# X15_Brickstribution.net
KiCad netlist of a schematic drawn in EAGLE
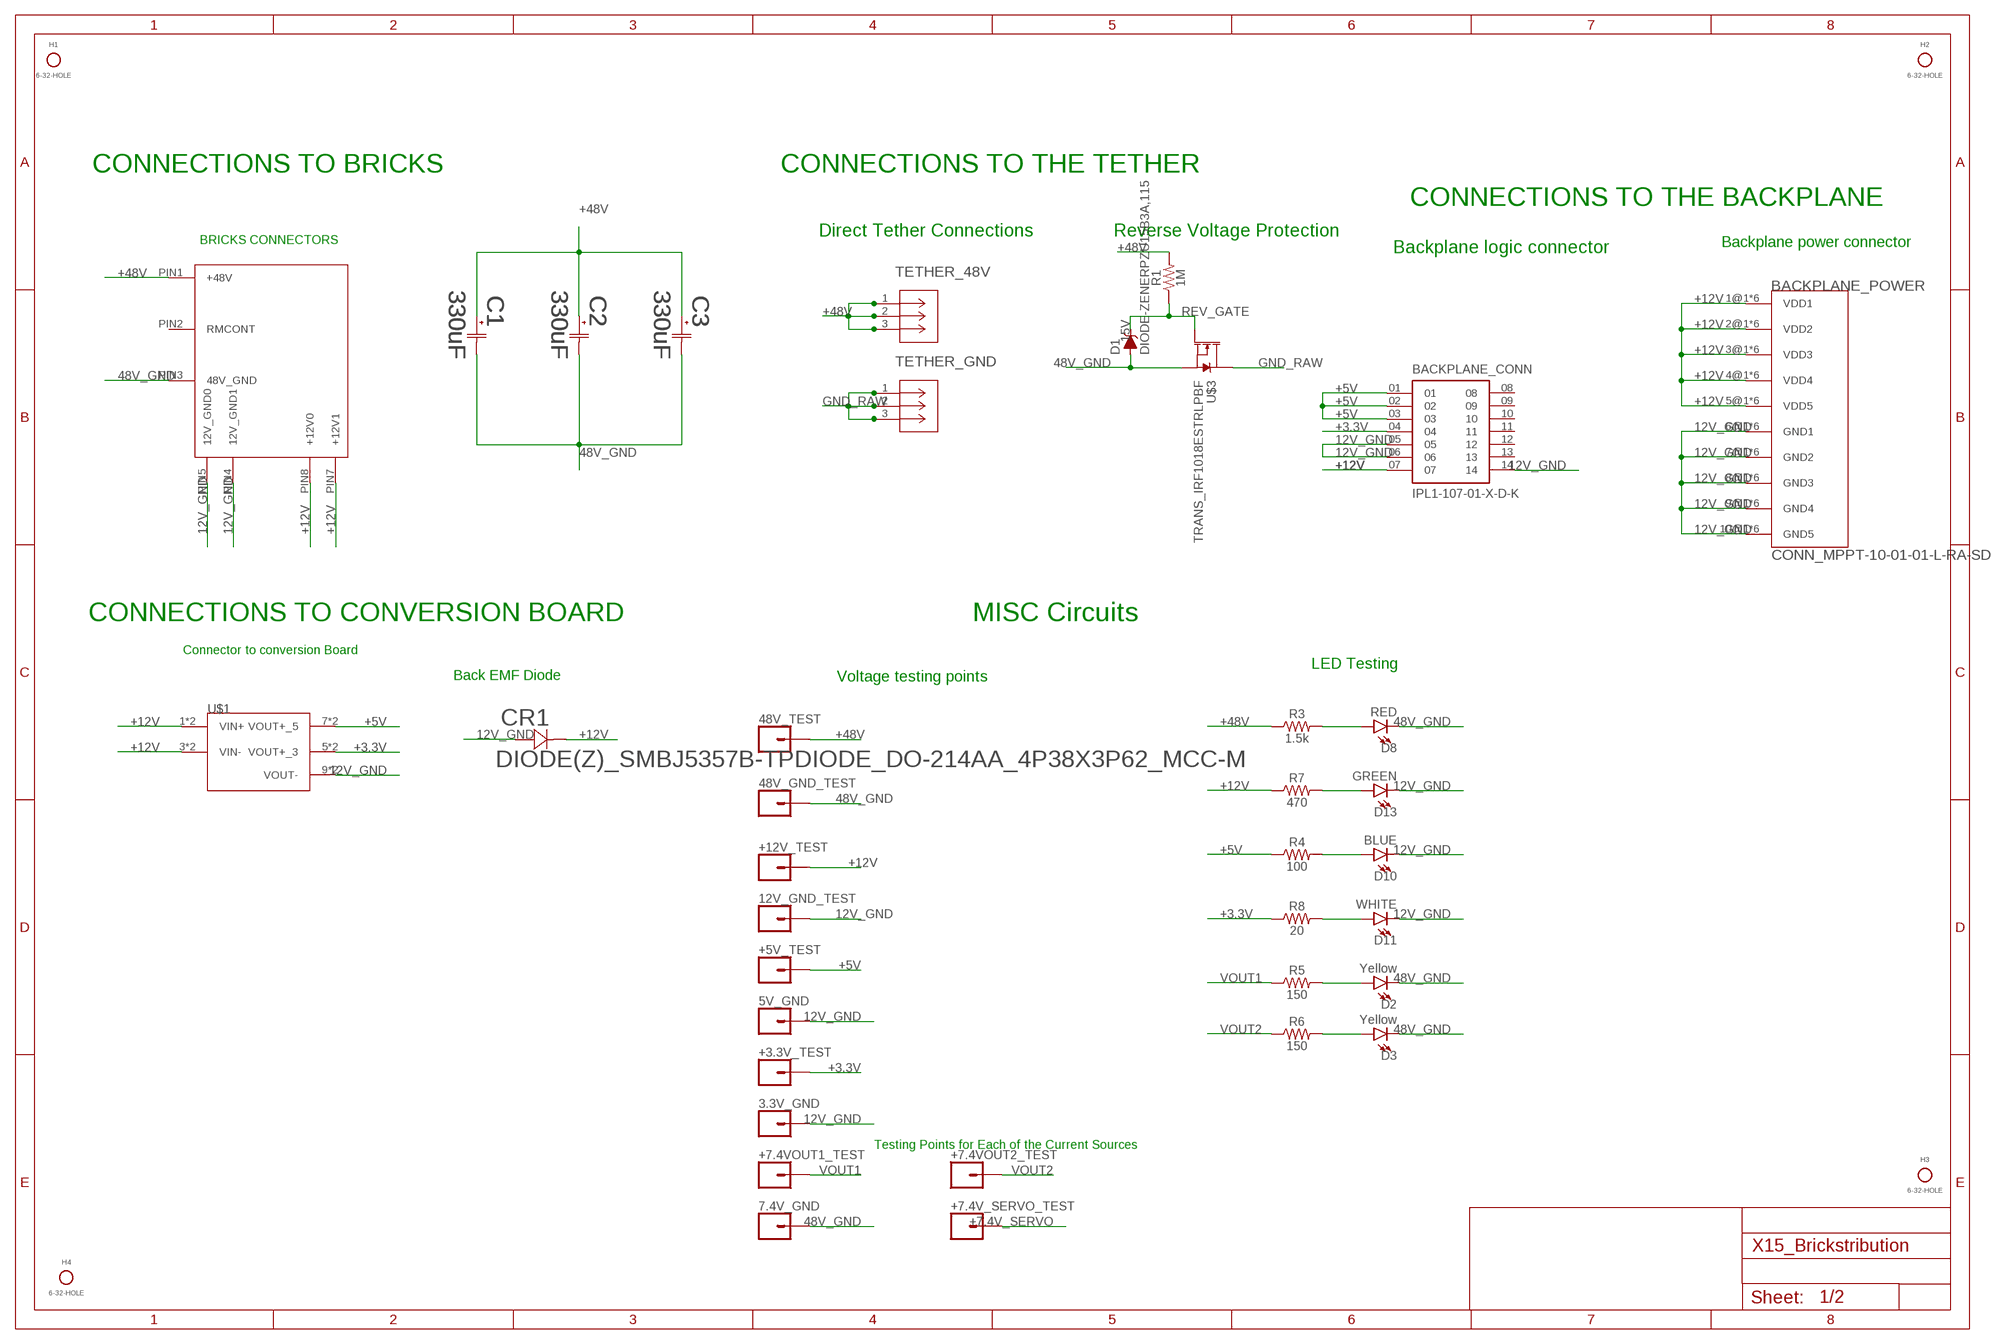
[diagram p0: schematic, sheet 1]
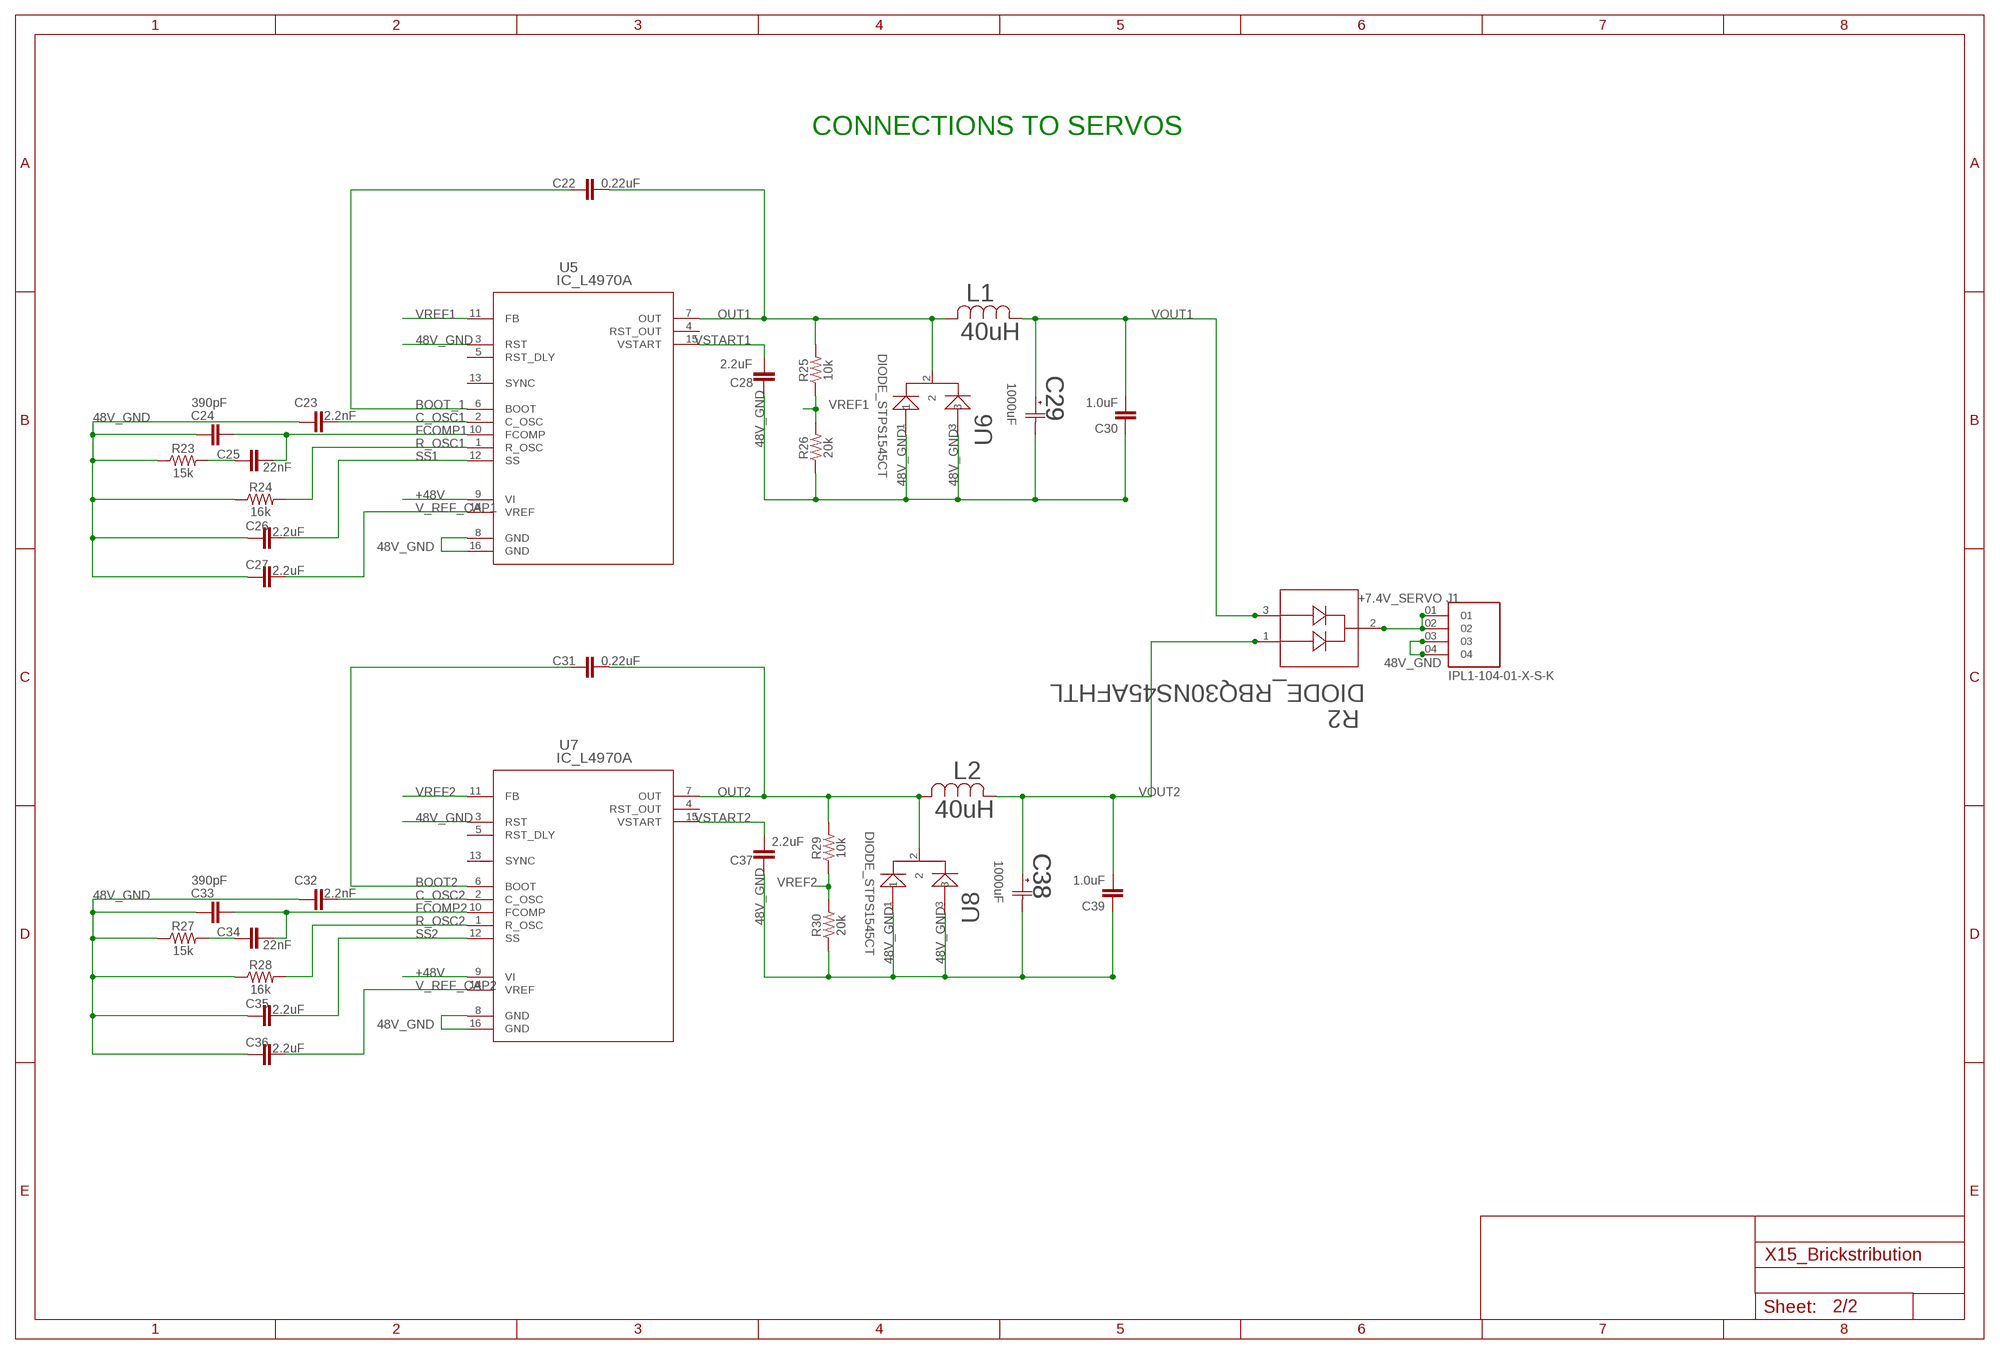
[diagram p1: schematic, sheet 2]

(export (version "E")
  (design (tool "Eeschema 10.0.6"))
  (components
    (comp (ref "C22")
      (value "0.22uF")
      (footprint "eagle-import:0603")
      (libsource (lib "eagle-import") (part "0.22UF-0603-25V-10%"))
    )
    (comp (ref "C23")
      (value "2.2nF")
      (footprint "eagle-import:0603")
      (libsource (lib "eagle-import") (part "2.2NF/2200PF-0603-50V-10%"))
    )
    (comp (ref "C24")
      (value "390pF")
      (footprint "eagle-import:0603")
      (libsource (lib "eagle-import") (part "390NF-0603-10V-10%"))
    )
    (comp (ref "C25")
      (value "22nF")
      (footprint "eagle-import:0603")
      (libsource (lib "eagle-import") (part "22NF/22,000PF-0603-50V-10%"))
    )
    (comp (ref "C26")
      (value "2.2uF")
      (footprint "eagle-import:0603")
      (libsource (lib "eagle-import") (part "2.2UF-0603-10V-20%"))
    )
    (comp (ref "C27")
      (value "2.2uF")
      (footprint "eagle-import:0603")
      (libsource (lib "eagle-import") (part "2.2UF-0603-10V-20%"))
    )
    (comp (ref "C28")
      (value "2.2uF")
      (footprint "eagle-import:0603")
      (libsource (lib "eagle-import") (part "2.2UF-0603-10V-20%"))
    )
    (comp (ref "C29")
      (value "1000uF")
      (footprint "eagle-import:CAP_PC_10X12P7_NCH-M")
      (fields
        (field (name "MANUFACTURER_PART_NUMBER") "PCG1A102MCL1GS")
        (field (name "COPYRIGHT") "Copyright (C) 2022 Ultra Librarian. All rights reserved.")
      )
      (libsource (lib "eagle-import") (part "CAP_PCG1A102MCL1GSCAP_PC_10X12P7_NCH-M"))
    )
    (comp (ref "C30")
      (value "1.0uF")
      (footprint "eagle-import:0603")
      (libsource (lib "eagle-import") (part "1.0UF-0603-16V-10%"))
    )
    (comp (ref "C31")
      (value "0.22uF")
      (footprint "eagle-import:0603")
      (libsource (lib "eagle-import") (part "0.22UF-0603-25V-10%"))
    )
    (comp (ref "C32")
      (value "2.2nF")
      (footprint "eagle-import:0603")
      (libsource (lib "eagle-import") (part "2.2NF/2200PF-0603-50V-10%"))
    )
    (comp (ref "C33")
      (value "390pF")
      (footprint "eagle-import:0603")
      (libsource (lib "eagle-import") (part "390NF-0603-10V-10%"))
    )
    (comp (ref "C34")
      (value "22nF")
      (footprint "eagle-import:0603")
      (libsource (lib "eagle-import") (part "22NF/22,000PF-0603-50V-10%"))
    )
    (comp (ref "C35")
      (value "2.2uF")
      (footprint "eagle-import:0603")
      (libsource (lib "eagle-import") (part "2.2UF-0603-10V-20%"))
    )
    (comp (ref "C36")
      (value "2.2uF")
      (footprint "eagle-import:0603")
      (libsource (lib "eagle-import") (part "2.2UF-0603-10V-20%"))
    )
    (comp (ref "C37")
      (value "2.2uF")
      (footprint "eagle-import:0603")
      (libsource (lib "eagle-import") (part "2.2UF-0603-10V-20%"))
    )
    (comp (ref "C38")
      (value "1000uF")
      (footprint "eagle-import:CAP_PC_10X12P7_NCH-M")
      (fields
        (field (name "MANUFACTURER_PART_NUMBER") "PCG1A102MCL1GS")
        (field (name "COPYRIGHT") "Copyright (C) 2022 Ultra Librarian. All rights reserved.")
      )
      (libsource (lib "eagle-import") (part "CAP_PCG1A102MCL1GSCAP_PC_10X12P7_NCH-M"))
    )
    (comp (ref "C39")
      (value "1.0uF")
      (footprint "eagle-import:0603")
      (libsource (lib "eagle-import") (part "1.0UF-0603-16V-10%"))
    )
    (comp (ref "J1")
      (value "IPL1-104-01-X-S-K")
      (footprint "eagle-import:SAMTEC_IPL1-104-01-X-S-K")
      (fields (field (name "MANUFACTURER") "SAMTEC"))
      (libsource (lib "eagle-import") (part "IPL1-104-01-X-S-K"))
    )
    (comp (ref "L1")
      (value "40uH")
      (footprint "eagle-import:IND_23XX-V_53_53")
      (fields
        (field (name "MANUFACTURER_PART_NUMBER") "2308-V-RC")
        (field (name "COPYRIGHT") "Copyright (C) 2022 Ultra Librarian. All rights reserved.")
      )
      (libsource (lib "eagle-import") (part "IND_2308-V-RC"))
    )
    (comp (ref "L2")
      (value "40uH")
      (footprint "eagle-import:IND_23XX-V_53_53")
      (fields
        (field (name "MANUFACTURER_PART_NUMBER") "2308-V-RC")
        (field (name "COPYRIGHT") "Copyright (C) 2022 Ultra Librarian. All rights reserved.")
      )
      (libsource (lib "eagle-import") (part "IND_2308-V-RC"))
    )
    (comp (ref "R2")
      (value "DIODE_RBQ30NS45AFHTL")
      (footprint "eagle-import:TRANS_R5009FNJ_ROM")
      (fields
        (field (name "MANUFACTURER_PART_NUMBER") "RBQ30NS45AFHTL")
        (field (name "COPYRIGHT") "Copyright (C) 2022 Ultra Librarian. All rights reserved.")
      )
      (libsource (lib "eagle-import") (part "DIODE_RBQ30NS45AFHTL"))
    )
    (comp (ref "R23")
      (value "15k")
      (footprint "eagle-import:0603")
      (libsource (lib "eagle-import") (part "15KOHM-0603-1/10W-1%"))
    )
    (comp (ref "R24")
      (value "16k")
      (footprint "eagle-import:0603")
      (libsource (lib "eagle-import") (part "16.2KOHM-0603-1/10W-1%"))
    )
    (comp (ref "R25")
      (value "10k")
      (footprint "eagle-import:0603")
      (libsource (lib "eagle-import") (part "10KOHM-0603-1/10W-1%"))
    )
    (comp (ref "R26")
      (value "20k")
      (footprint "eagle-import:0603")
      (libsource (lib "eagle-import") (part "20KOHM-0603-1/10W-1%"))
    )
    (comp (ref "R27")
      (value "15k")
      (footprint "eagle-import:0603")
      (libsource (lib "eagle-import") (part "15KOHM-0603-1/10W-1%"))
    )
    (comp (ref "R28")
      (value "16k")
      (footprint "eagle-import:0603")
      (libsource (lib "eagle-import") (part "16.2KOHM-0603-1/10W-1%"))
    )
    (comp (ref "R29")
      (value "10k")
      (footprint "eagle-import:0603")
      (libsource (lib "eagle-import") (part "10KOHM-0603-1/10W-1%"))
    )
    (comp (ref "R30")
      (value "20k")
      (footprint "eagle-import:0603")
      (libsource (lib "eagle-import") (part "20KOHM-0603-1/10W-1%"))
    )
    (comp (ref "U5")
      (value "IC_L4970A")
      (footprint "eagle-import:MULTIWATT15_V_STM")
      (fields
        (field (name "MANUFACTURER_PART_NUMBER") "L4970A")
        (field (name "COPYRIGHT") "Copyright (C) 2022 Ultra Librarian. All rights reserved.")
      )
      (libsource (lib "eagle-import") (part "IC_L4970A"))
    )
    (comp (ref "U6")
      (value "DIODE_STPS1545CT")
      (footprint "eagle-import:TO-220AB_STM")
      (fields
        (field (name "MANUFACTURER_PART_NUMBER") "STPS1545CT")
        (field (name "COPYRIGHT") "Copyright (C) 2022 Ultra Librarian. All rights reserved.")
      )
      (libsource (lib "eagle-import") (part "DIODE_STPS1545CT"))
    )
    (comp (ref "U7")
      (value "IC_L4970A")
      (footprint "eagle-import:MULTIWATT15_V_STM")
      (fields
        (field (name "MANUFACTURER_PART_NUMBER") "L4970A")
        (field (name "COPYRIGHT") "Copyright (C) 2022 Ultra Librarian. All rights reserved.")
      )
      (libsource (lib "eagle-import") (part "IC_L4970A"))
    )
    (comp (ref "U8")
      (value "DIODE_STPS1545CT")
      (footprint "eagle-import:TO-220AB_STM")
      (fields
        (field (name "MANUFACTURER_PART_NUMBER") "STPS1545CT")
        (field (name "COPYRIGHT") "Copyright (C) 2022 Ultra Librarian. All rights reserved.")
      )
      (libsource (lib "eagle-import") (part "DIODE_STPS1545CT"))
    )
    (comp (ref "+3.3V_TEST")
      (value "CONN_01")
      (footprint "eagle-import:1X01")
      (libsource (lib "eagle-import") (part "CONN_01"))
    )
    (comp (ref "+5V_TEST")
      (value "CONN_01")
      (footprint "eagle-import:1X01")
      (libsource (lib "eagle-import") (part "CONN_01"))
    )
    (comp (ref "+7.4VOUT1_TEST")
      (value "CONN_01")
      (footprint "eagle-import:1X01")
      (libsource (lib "eagle-import") (part "CONN_01"))
    )
    (comp (ref "+7.4VOUT2_TEST")
      (value "CONN_01")
      (footprint "eagle-import:1X01")
      (libsource (lib "eagle-import") (part "CONN_01"))
    )
    (comp (ref "+7.4V_SERVO_TEST")
      (value "CONN_01")
      (footprint "eagle-import:1X01")
      (libsource (lib "eagle-import") (part "CONN_01"))
    )
    (comp (ref "+12V_TEST")
      (value "CONN_01")
      (footprint "eagle-import:1X01")
      (libsource (lib "eagle-import") (part "CONN_01"))
    )
    (comp (ref "3.3V_GND")
      (value "CONN_01")
      (footprint "eagle-import:1X01")
      (libsource (lib "eagle-import") (part "CONN_01"))
    )
    (comp (ref "5V_GND")
      (value "CONN_01")
      (footprint "eagle-import:1X01")
      (libsource (lib "eagle-import") (part "CONN_01"))
    )
    (comp (ref "7.4V_GND")
      (value "CONN_01")
      (footprint "eagle-import:1X01")
      (libsource (lib "eagle-import") (part "CONN_01"))
    )
    (comp (ref "12V_GND_TEST")
      (value "CONN_01")
      (footprint "eagle-import:1X01")
      (libsource (lib "eagle-import") (part "CONN_01"))
    )
    (comp (ref "48V_GND_TEST")
      (value "CONN_01")
      (footprint "eagle-import:1X01")
      (libsource (lib "eagle-import") (part "CONN_01"))
    )
    (comp (ref "48V_TEST")
      (value "CONN_01")
      (footprint "eagle-import:1X01")
      (libsource (lib "eagle-import") (part "CONN_01"))
    )
    (comp (ref "BACKPLANE_CONN")
      (value "IPL1-107-01-X-D-K")
      (footprint "eagle-import:SAMTEC_IPL1-107-01-X-D-K")
      (libsource (lib "eagle-import") (part "IPL1-107-01-X-D-K"))
    )
    (comp (ref "BACKPLANE_POWER")
      (value "CONN_MPPT-10-01-01-L-RA-SD")
      (footprint "eagle-import:MPPT-10-01-01-L-RA-SD")
      (libsource (lib "eagle-import") (part "CONN_MPPT-10-01-01-L-RA-SD"))
    )
    (comp (ref "C1")
      (value "330uF")
      (footprint "eagle-import:CAP_099112E3_VIS-M")
      (fields
        (field (name "MANUFACTURER_PART_NUMBER") "MAL215099112E3")
        (field (name "COPYRIGHT") "Copyright (C) 2022 Ultra Librarian. All rights reserved.")
      )
      (libsource (lib "eagle-import") (part "CAP_MAL215099112E3CAP_099112E3_VIS-M"))
    )
    (comp (ref "C2")
      (value "330uF")
      (footprint "eagle-import:CAP_099112E3_VIS-M")
      (fields
        (field (name "MANUFACTURER_PART_NUMBER") "MAL215099112E3")
        (field (name "COPYRIGHT") "Copyright (C) 2022 Ultra Librarian. All rights reserved.")
      )
      (libsource (lib "eagle-import") (part "CAP_MAL215099112E3CAP_099112E3_VIS-M"))
    )
    (comp (ref "C3")
      (value "330uF")
      (footprint "eagle-import:CAP_099112E3_VIS-M")
      (fields
        (field (name "MANUFACTURER_PART_NUMBER") "MAL215099112E3")
        (field (name "COPYRIGHT") "Copyright (C) 2022 Ultra Librarian. All rights reserved.")
      )
      (libsource (lib "eagle-import") (part "CAP_MAL215099112E3CAP_099112E3_VIS-M"))
    )
    (comp (ref "CR1")
      (value "DIODE(Z)_SMBJ5357B-TPDIODE_DO-214AA_4P38X3P62_MCC-M")
      (footprint "eagle-import:DIODE_DO-214AA_4P38X3P62_MCC-M")
      (fields
        (field (name "MANUFACTURER_PART_NUMBER") "SMBJ5357B-TP")
        (field (name "COPYRIGHT") "Copyright (C) 2022 Ultra Librarian. All rights reserved.")
      )
      (libsource (lib "eagle-import") (part "DIODE(Z)_SMBJ5357B-TPDIODE_DO-214AA_4P38X3P62_MCC-M"))
    )
    (comp (ref "D1")
      (value "DIODE-ZENERPZU15B3A,115")
      (footprint "eagle-import:SOD-323")
      (fields (field (name "ZENER_VOLTAGE") "15V"))
      (libsource (lib "eagle-import") (part "DIODE-ZENERPZU15B3A,115"))
    )
    (comp (ref "D2")
      (value "Yellow")
      (footprint "eagle-import:LED-0603")
      (libsource (lib "eagle-import") (part "LED-YELLOW0603"))
    )
    (comp (ref "D3")
      (value "Yellow")
      (footprint "eagle-import:LED-0603")
      (libsource (lib "eagle-import") (part "LED-YELLOW0603"))
    )
    (comp (ref "D8")
      (value "RED")
      (footprint "eagle-import:LED-0603")
      (libsource (lib "eagle-import") (part "LED-RED0603"))
    )
    (comp (ref "D10")
      (value "BLUE")
      (footprint "eagle-import:LED-0603")
      (libsource (lib "eagle-import") (part "LED-BLUE0603"))
    )
    (comp (ref "D11")
      (value "WHITE")
      (footprint "eagle-import:LED-0603")
      (libsource (lib "eagle-import") (part "LED-WHITE0603"))
    )
    (comp (ref "D13")
      (value "GREEN")
      (footprint "eagle-import:LED-0603")
      (libsource (lib "eagle-import") (part "LED-GREEN0603"))
    )
    (comp (ref "H1")
      (value "6-32-HOLE")
      (footprint "eagle-import:6-32-HOLE")
      (libsource (lib "eagle-import") (part "6-32-HOLE"))
    )
    (comp (ref "H2")
      (value "6-32-HOLE")
      (footprint "eagle-import:6-32-HOLE")
      (libsource (lib "eagle-import") (part "6-32-HOLE"))
    )
    (comp (ref "H3")
      (value "6-32-HOLE")
      (footprint "eagle-import:6-32-HOLE")
      (libsource (lib "eagle-import") (part "6-32-HOLE"))
    )
    (comp (ref "H4")
      (value "6-32-HOLE")
      (footprint "eagle-import:6-32-HOLE")
      (libsource (lib "eagle-import") (part "6-32-HOLE"))
    )
    (comp (ref "R1")
      (value "1M")
      (footprint "eagle-import:0603")
      (libsource (lib "eagle-import") (part "1MOHM-0603-1/4W-5%"))
    )
    (comp (ref "R3")
      (value "1.5k")
      (footprint "eagle-import:0603")
      (libsource (lib "eagle-import") (part "1.5KOHM-0603-1/10W-1%"))
    )
    (comp (ref "R4")
      (value "100")
      (footprint "eagle-import:0603")
      (libsource (lib "eagle-import") (part "100OHM-0603-1/4W-5%"))
    )
    (comp (ref "R5")
      (value "150")
      (footprint "eagle-import:0603")
      (libsource (lib "eagle-import") (part "150OHM-0603-1/10W-1%"))
    )
    (comp (ref "R6")
      (value "150")
      (footprint "eagle-import:0603")
      (libsource (lib "eagle-import") (part "150OHM-0603-1/10W-1%"))
    )
    (comp (ref "R7")
      (value "470")
      (footprint "eagle-import:0603")
      (libsource (lib "eagle-import") (part "470OHM-0603-1/10W-1%"))
    )
    (comp (ref "R8")
      (value "20")
      (footprint "eagle-import:0603")
      (libsource (lib "eagle-import") (part "20OHM-0603-1/10W-1%"))
    )
    (comp (ref "TETHER_48V")
      (value "796636-3(TETHER)")
      (footprint "eagle-import:CON3_P5MM_VER_TERM-BLK_TYC")
      (fields
        (field (name "MANUFACTURER_PART_NUMBER") "796636-3")
        (field (name "COPYRIGHT") "Copyright (C) 2022 Ultra Librarian. All rights reserved.")
      )
      (libsource (lib "eagle-import") (part "796636-3(TETHER)"))
    )
    (comp (ref "TETHER_GND")
      (value "796636-3(TETHER)")
      (footprint "eagle-import:CON3_P5MM_VER_TERM-BLK_TYC")
      (fields
        (field (name "MANUFACTURER_PART_NUMBER") "796636-3")
        (field (name "COPYRIGHT") "Copyright (C) 2022 Ultra Librarian. All rights reserved.")
      )
      (libsource (lib "eagle-import") (part "796636-3(TETHER)"))
    )
    (comp (ref "U$1")
      (value "CONN_DISTRIBUTION_TO_CONVERSION")
      (footprint "eagle-import:TSW-105-05-G-S(D-C)")
      (libsource (lib "eagle-import") (part "CONN_DISTRIBUTION_TO_CONVERSION"))
    )
    (comp (ref "U$2")
      (value "CONN_BMR480_CONNECTOR")
      (footprint "eagle-import:BMR480_CONNECTOR")
      (libsource (lib "eagle-import") (part "CONN_BMR480_CONNECTOR"))
    )
    (comp (ref "U$3")
      (value "TRANS_IRF1018ESTRLPBF")
      (footprint "eagle-import:D2PAK")
      (libsource (lib "eagle-import") (part "TRANS_IRF1018EPBF"))
    )
  )
  (nets
    (net (code "1") (name "+3.3V") (class "Default")
      (node (ref "+3.3V_TEST") (pin "1") (pinfunction "1_1") (pintype "passive"))
      (node (ref "BACKPLANE_CONN") (pin "04") (pinfunction "04_04") (pintype "passive"))
      (node (ref "R8") (pin "1") (pinfunction "1_1") (pintype "passive"))
      (node (ref "U$1") (pin "5") (pinfunction "VOUT+_3_5") (pintype "bidirectional"))
      (node (ref "U$1") (pin "6") (pinfunction "VOUT+_3_6") (pintype "bidirectional"))
    )
    (net (code "2") (name "+5V") (class "Default")
      (node (ref "+5V_TEST") (pin "1") (pinfunction "1_1") (pintype "passive"))
      (node (ref "BACKPLANE_CONN") (pin "01") (pinfunction "01_01") (pintype "passive"))
      (node (ref "BACKPLANE_CONN") (pin "02") (pinfunction "02_02") (pintype "passive"))
      (node (ref "BACKPLANE_CONN") (pin "03") (pinfunction "03_03") (pintype "passive"))
      (node (ref "R4") (pin "1") (pinfunction "1_1") (pintype "passive"))
      (node (ref "U$1") (pin "7") (pinfunction "VOUT+_5_7") (pintype "bidirectional"))
      (node (ref "U$1") (pin "8") (pinfunction "VOUT+_5_8") (pintype "bidirectional"))
    )
    (net (code "3") (name "+7.4V_SERVO") (class "Default")
      (node (ref "+7.4V_SERVO_TEST") (pin "1") (pinfunction "1_1") (pintype "passive"))
      (node (ref "J1") (pin "01") (pinfunction "01_01") (pintype "passive"))
      (node (ref "J1") (pin "02") (pinfunction "02_02") (pintype "passive"))
      (node (ref "R2") (pin "2") (pinfunction "2_2") (pintype "passive"))
    )
    (net (code "4") (name "+12V") (class "Default")
      (node (ref "+12V_TEST") (pin "1") (pinfunction "1_1") (pintype "passive"))
      (node (ref "BACKPLANE_CONN") (pin "07") (pinfunction "07_07") (pintype "passive"))
      (node (ref "BACKPLANE_POWER") (pin "1@1") (pinfunction "VDD1_1@1") (pintype "bidirectional"))
      (node (ref "BACKPLANE_POWER") (pin "1@2") (pinfunction "VDD1_1@2") (pintype "bidirectional"))
      (node (ref "BACKPLANE_POWER") (pin "1@3") (pinfunction "VDD1_1@3") (pintype "bidirectional"))
      (node (ref "BACKPLANE_POWER") (pin "1@4") (pinfunction "VDD1_1@4") (pintype "bidirectional"))
      (node (ref "BACKPLANE_POWER") (pin "1@5") (pinfunction "VDD1_1@5") (pintype "bidirectional"))
      (node (ref "BACKPLANE_POWER") (pin "1@6") (pinfunction "VDD1_1@6") (pintype "bidirectional"))
      (node (ref "BACKPLANE_POWER") (pin "2@1") (pinfunction "VDD2_2@1") (pintype "bidirectional"))
      (node (ref "BACKPLANE_POWER") (pin "2@2") (pinfunction "VDD2_2@2") (pintype "bidirectional"))
      (node (ref "BACKPLANE_POWER") (pin "2@3") (pinfunction "VDD2_2@3") (pintype "bidirectional"))
      (node (ref "BACKPLANE_POWER") (pin "2@4") (pinfunction "VDD2_2@4") (pintype "bidirectional"))
      (node (ref "BACKPLANE_POWER") (pin "2@5") (pinfunction "VDD2_2@5") (pintype "bidirectional"))
      (node (ref "BACKPLANE_POWER") (pin "2@6") (pinfunction "VDD2_2@6") (pintype "bidirectional"))
      (node (ref "BACKPLANE_POWER") (pin "3@1") (pinfunction "VDD3_3@1") (pintype "bidirectional"))
      (node (ref "BACKPLANE_POWER") (pin "3@2") (pinfunction "VDD3_3@2") (pintype "bidirectional"))
      (node (ref "BACKPLANE_POWER") (pin "3@3") (pinfunction "VDD3_3@3") (pintype "bidirectional"))
      (node (ref "BACKPLANE_POWER") (pin "3@4") (pinfunction "VDD3_3@4") (pintype "bidirectional"))
      (node (ref "BACKPLANE_POWER") (pin "3@5") (pinfunction "VDD3_3@5") (pintype "bidirectional"))
      (node (ref "BACKPLANE_POWER") (pin "3@6") (pinfunction "VDD3_3@6") (pintype "bidirectional"))
      (node (ref "BACKPLANE_POWER") (pin "4@1") (pinfunction "VDD4_4@1") (pintype "bidirectional"))
      (node (ref "BACKPLANE_POWER") (pin "4@2") (pinfunction "VDD4_4@2") (pintype "bidirectional"))
      (node (ref "BACKPLANE_POWER") (pin "4@3") (pinfunction "VDD4_4@3") (pintype "bidirectional"))
      (node (ref "BACKPLANE_POWER") (pin "4@4") (pinfunction "VDD4_4@4") (pintype "bidirectional"))
      (node (ref "BACKPLANE_POWER") (pin "4@5") (pinfunction "VDD4_4@5") (pintype "bidirectional"))
      (node (ref "BACKPLANE_POWER") (pin "4@6") (pinfunction "VDD4_4@6") (pintype "bidirectional"))
      (node (ref "BACKPLANE_POWER") (pin "5@1") (pinfunction "VDD5_5@1") (pintype "bidirectional"))
      (node (ref "BACKPLANE_POWER") (pin "5@2") (pinfunction "VDD5_5@2") (pintype "bidirectional"))
      (node (ref "BACKPLANE_POWER") (pin "5@3") (pinfunction "VDD5_5@3") (pintype "bidirectional"))
      (node (ref "BACKPLANE_POWER") (pin "5@4") (pinfunction "VDD5_5@4") (pintype "bidirectional"))
      (node (ref "BACKPLANE_POWER") (pin "5@5") (pinfunction "VDD5_5@5") (pintype "bidirectional"))
      (node (ref "BACKPLANE_POWER") (pin "5@6") (pinfunction "VDD5_5@6") (pintype "bidirectional"))
      (node (ref "CR1") (pin "1") (pinfunction "1_1") (pintype "passive"))
      (node (ref "R7") (pin "1") (pinfunction "1_1") (pintype "passive"))
      (node (ref "U$1") (pin "1") (pinfunction "VIN+_1") (pintype "bidirectional"))
      (node (ref "U$1") (pin "2") (pinfunction "VIN+_2") (pintype "bidirectional"))
      (node (ref "U$1") (pin "3") (pinfunction "VIN-_3") (pintype "bidirectional"))
      (node (ref "U$1") (pin "4") (pinfunction "VIN-_4") (pintype "bidirectional"))
      (node (ref "U$2") (pin "PIN7") (pinfunction "+12V1_PIN7") (pintype "bidirectional"))
      (node (ref "U$2") (pin "PIN8") (pinfunction "+12V0_PIN8") (pintype "bidirectional"))
    )
    (net (code "5") (name "+48V") (class "Default")
      (node (ref "48V_TEST") (pin "1") (pinfunction "1_1") (pintype "passive"))
      (node (ref "C1") (pin "1") (pinfunction "1_1") (pintype "passive"))
      (node (ref "C2") (pin "1") (pinfunction "1_1") (pintype "passive"))
      (node (ref "C3") (pin "1") (pinfunction "1_1") (pintype "passive"))
      (node (ref "R1") (pin "2") (pinfunction "2_2") (pintype "passive"))
      (node (ref "R3") (pin "1") (pinfunction "1_1") (pintype "passive"))
      (node (ref "TETHER_48V") (pin "1") (pinfunction "1_1") (pintype "passive"))
      (node (ref "TETHER_48V") (pin "2") (pinfunction "2_2") (pintype "passive"))
      (node (ref "TETHER_48V") (pin "3") (pinfunction "3_3") (pintype "passive"))
      (node (ref "U$2") (pin "PIN1") (pinfunction "+48V_PIN1") (pintype "bidirectional"))
      (node (ref "U5") (pin "9") (pinfunction "VI_9") (pintype "power_in"))
      (node (ref "U7") (pin "9") (pinfunction "VI_9") (pintype "power_in"))
    )
    (net (code "6") (name "12V_GND") (class "Default")
      (node (ref "12V_GND_TEST") (pin "1") (pinfunction "1_1") (pintype "passive"))
      (node (ref "3.3V_GND") (pin "1") (pinfunction "1_1") (pintype "passive"))
      (node (ref "5V_GND") (pin "1") (pinfunction "1_1") (pintype "passive"))
      (node (ref "BACKPLANE_CONN") (pin "05") (pinfunction "05_05") (pintype "passive"))
      (node (ref "BACKPLANE_CONN") (pin "06") (pinfunction "06_06") (pintype "passive"))
      (node (ref "BACKPLANE_CONN") (pin "14") (pinfunction "14_14") (pintype "passive"))
      (node (ref "BACKPLANE_POWER") (pin "10@1") (pinfunction "GND5_10@1") (pintype "bidirectional"))
      (node (ref "BACKPLANE_POWER") (pin "10@2") (pinfunction "GND5_10@2") (pintype "bidirectional"))
      (node (ref "BACKPLANE_POWER") (pin "10@3") (pinfunction "GND5_10@3") (pintype "bidirectional"))
      (node (ref "BACKPLANE_POWER") (pin "10@4") (pinfunction "GND5_10@4") (pintype "bidirectional"))
      (node (ref "BACKPLANE_POWER") (pin "10@5") (pinfunction "GND5_10@5") (pintype "bidirectional"))
      (node (ref "BACKPLANE_POWER") (pin "10@6") (pinfunction "GND5_10@6") (pintype "bidirectional"))
      (node (ref "BACKPLANE_POWER") (pin "6@1") (pinfunction "GND1_6@1") (pintype "bidirectional"))
      (node (ref "BACKPLANE_POWER") (pin "6@2") (pinfunction "GND1_6@2") (pintype "bidirectional"))
      (node (ref "BACKPLANE_POWER") (pin "6@3") (pinfunction "GND1_6@3") (pintype "bidirectional"))
      (node (ref "BACKPLANE_POWER") (pin "6@4") (pinfunction "GND1_6@4") (pintype "bidirectional"))
      (node (ref "BACKPLANE_POWER") (pin "6@5") (pinfunction "GND1_6@5") (pintype "bidirectional"))
      (node (ref "BACKPLANE_POWER") (pin "6@6") (pinfunction "GND1_6@6") (pintype "bidirectional"))
      (node (ref "BACKPLANE_POWER") (pin "7@1") (pinfunction "GND2_7@1") (pintype "bidirectional"))
      (node (ref "BACKPLANE_POWER") (pin "7@2") (pinfunction "GND2_7@2") (pintype "bidirectional"))
      (node (ref "BACKPLANE_POWER") (pin "7@3") (pinfunction "GND2_7@3") (pintype "bidirectional"))
      (node (ref "BACKPLANE_POWER") (pin "7@4") (pinfunction "GND2_7@4") (pintype "bidirectional"))
      (node (ref "BACKPLANE_POWER") (pin "7@5") (pinfunction "GND2_7@5") (pintype "bidirectional"))
      (node (ref "BACKPLANE_POWER") (pin "7@6") (pinfunction "GND2_7@6") (pintype "bidirectional"))
      (node (ref "BACKPLANE_POWER") (pin "8@1") (pinfunction "GND3_8@1") (pintype "bidirectional"))
      (node (ref "BACKPLANE_POWER") (pin "8@2") (pinfunction "GND3_8@2") (pintype "bidirectional"))
      (node (ref "BACKPLANE_POWER") (pin "8@3") (pinfunction "GND3_8@3") (pintype "bidirectional"))
      (node (ref "BACKPLANE_POWER") (pin "8@4") (pinfunction "GND3_8@4") (pintype "bidirectional"))
      (node (ref "BACKPLANE_POWER") (pin "8@5") (pinfunction "GND3_8@5") (pintype "bidirectional"))
      (node (ref "BACKPLANE_POWER") (pin "8@6") (pinfunction "GND3_8@6") (pintype "bidirectional"))
      (node (ref "BACKPLANE_POWER") (pin "9@1") (pinfunction "GND4_9@1") (pintype "bidirectional"))
      (node (ref "BACKPLANE_POWER") (pin "9@2") (pinfunction "GND4_9@2") (pintype "bidirectional"))
      (node (ref "BACKPLANE_POWER") (pin "9@3") (pinfunction "GND4_9@3") (pintype "bidirectional"))
      (node (ref "BACKPLANE_POWER") (pin "9@4") (pinfunction "GND4_9@4") (pintype "bidirectional"))
      (node (ref "BACKPLANE_POWER") (pin "9@5") (pinfunction "GND4_9@5") (pintype "bidirectional"))
      (node (ref "BACKPLANE_POWER") (pin "9@6") (pinfunction "GND4_9@6") (pintype "bidirectional"))
      (node (ref "CR1") (pin "2") (pinfunction "2_2") (pintype "passive"))
      (node (ref "D10") (pin "C") (pinfunction "C_C") (pintype "passive"))
      (node (ref "D11") (pin "C") (pinfunction "C_C") (pintype "passive"))
      (node (ref "D13") (pin "C") (pinfunction "C_C") (pintype "passive"))
      (node (ref "U$1") (pin "10") (pinfunction "VOUT-_10") (pintype "bidirectional"))
      (node (ref "U$1") (pin "9") (pinfunction "VOUT-_9") (pintype "bidirectional"))
      (node (ref "U$2") (pin "PIN4") (pinfunction "12V_GND1_PIN4") (pintype "bidirectional"))
      (node (ref "U$2") (pin "PIN5") (pinfunction "12V_GND0_PIN5") (pintype "bidirectional"))
    )
    (net (code "7") (name "48V_GND") (class "Default")
      (node (ref "48V_GND_TEST") (pin "1") (pinfunction "1_1") (pintype "passive"))
      (node (ref "7.4V_GND") (pin "1") (pinfunction "1_1") (pintype "passive"))
      (node (ref "C1") (pin "2") (pinfunction "2_2") (pintype "passive"))
      (node (ref "C2") (pin "2") (pinfunction "2_2") (pintype "passive"))
      (node (ref "C23") (pin "1") (pinfunction "1_1") (pintype "passive"))
      (node (ref "C24") (pin "1") (pinfunction "1_1") (pintype "passive"))
      (node (ref "C26") (pin "1") (pinfunction "1_1") (pintype "passive"))
      (node (ref "C27") (pin "1") (pinfunction "1_1") (pintype "passive"))
      (node (ref "C28") (pin "1") (pinfunction "1_1") (pintype "passive"))
      (node (ref "C29") (pin "2") (pinfunction "2_2") (pintype "passive"))
      (node (ref "C3") (pin "2") (pinfunction "2_2") (pintype "passive"))
      (node (ref "C30") (pin "1") (pinfunction "1_1") (pintype "passive"))
      (node (ref "C32") (pin "1") (pinfunction "1_1") (pintype "passive"))
      (node (ref "C33") (pin "1") (pinfunction "1_1") (pintype "passive"))
      (node (ref "C35") (pin "1") (pinfunction "1_1") (pintype "passive"))
      (node (ref "C36") (pin "1") (pinfunction "1_1") (pintype "passive"))
      (node (ref "C37") (pin "1") (pinfunction "1_1") (pintype "passive"))
      (node (ref "C38") (pin "2") (pinfunction "2_2") (pintype "passive"))
      (node (ref "C39") (pin "1") (pinfunction "1_1") (pintype "passive"))
      (node (ref "D1") (pin "A") (pinfunction "A_A") (pintype "passive"))
      (node (ref "D2") (pin "C") (pinfunction "C_C") (pintype "passive"))
      (node (ref "D3") (pin "C") (pinfunction "C_C") (pintype "passive"))
      (node (ref "D8") (pin "C") (pinfunction "C_C") (pintype "passive"))
      (node (ref "J1") (pin "03") (pinfunction "03_03") (pintype "passive"))
      (node (ref "J1") (pin "04") (pinfunction "04_04") (pintype "passive"))
      (node (ref "R23") (pin "1") (pinfunction "1_1") (pintype "passive"))
      (node (ref "R24") (pin "1") (pinfunction "1_1") (pintype "passive"))
      (node (ref "R26") (pin "1") (pinfunction "1_1") (pintype "passive"))
      (node (ref "R27") (pin "1") (pinfunction "1_1") (pintype "passive"))
      (node (ref "R28") (pin "1") (pinfunction "1_1") (pintype "passive"))
      (node (ref "R30") (pin "1") (pinfunction "1_1") (pintype "passive"))
      (node (ref "U$2") (pin "PIN3") (pinfunction "48V_GND_PIN3") (pintype "bidirectional"))
      (node (ref "U$3") (pin "2") (pinfunction "S_2") (pintype "bidirectional"))
      (node (ref "U5") (pin "16") (pinfunction "GND_16") (pintype "bidirectional"))
      (node (ref "U5") (pin "3") (pinfunction "RST_3") (pintype "input"))
      (node (ref "U5") (pin "8") (pinfunction "GND_8") (pintype "power_in"))
      (node (ref "U6") (pin "1") (pinfunction "1_1") (pintype "passive"))
      (node (ref "U6") (pin "3") (pinfunction "3_3") (pintype "passive"))
      (node (ref "U7") (pin "16") (pinfunction "GND_16") (pintype "bidirectional"))
      (node (ref "U7") (pin "3") (pinfunction "RST_3") (pintype "input"))
      (node (ref "U7") (pin "8") (pinfunction "GND_8") (pintype "power_in"))
      (node (ref "U8") (pin "1") (pinfunction "1_1") (pintype "passive"))
      (node (ref "U8") (pin "3") (pinfunction "3_3") (pintype "passive"))
    )
    (net (code "8") (name "BOOT2") (class "Default")
      (node (ref "C31") (pin "1") (pinfunction "1_1") (pintype "passive"))
      (node (ref "U7") (pin "6") (pinfunction "BOOT_6") (pintype "passive"))
    )
    (net (code "9") (name "BOOT_1") (class "Default")
      (node (ref "C22") (pin "1") (pinfunction "1_1") (pintype "passive"))
      (node (ref "U5") (pin "6") (pinfunction "BOOT_6") (pintype "passive"))
    )
    (net (code "10") (name "C_OSC1") (class "Default")
      (node (ref "C23") (pin "2") (pinfunction "2_2") (pintype "passive"))
      (node (ref "U5") (pin "2") (pinfunction "C_OSC_2") (pintype "passive"))
    )
    (net (code "11") (name "C_OSC2") (class "Default")
      (node (ref "C32") (pin "2") (pinfunction "2_2") (pintype "passive"))
      (node (ref "U7") (pin "2") (pinfunction "C_OSC_2") (pintype "passive"))
    )
    (net (code "12") (name "FCOMP1") (class "Default")
      (node (ref "C24") (pin "2") (pinfunction "2_2") (pintype "passive"))
      (node (ref "C25") (pin "2") (pinfunction "2_2") (pintype "passive"))
      (node (ref "U5") (pin "10") (pinfunction "FCOMP_10") (pintype "passive"))
    )
    (net (code "13") (name "FCOMP2") (class "Default")
      (node (ref "C33") (pin "2") (pinfunction "2_2") (pintype "passive"))
      (node (ref "C34") (pin "2") (pinfunction "2_2") (pintype "passive"))
      (node (ref "U7") (pin "10") (pinfunction "FCOMP_10") (pintype "passive"))
    )
    (net (code "14") (name "GND_RAW") (class "Default")
      (node (ref "TETHER_GND") (pin "1") (pinfunction "1_1") (pintype "passive"))
      (node (ref "TETHER_GND") (pin "2") (pinfunction "2_2") (pintype "passive"))
      (node (ref "TETHER_GND") (pin "3") (pinfunction "3_3") (pintype "passive"))
      (node (ref "U$3") (pin "3") (pinfunction "D_3") (pintype "bidirectional"))
    )
    (net (code "15") (name "Net-(C25-Pad1)") (class "Default")
      (node (ref "C25") (pin "1") (pinfunction "1_1") (pintype "passive"))
      (node (ref "R23") (pin "2") (pinfunction "2_2") (pintype "passive"))
    )
    (net (code "16") (name "Net-(C34-Pad1)") (class "Default")
      (node (ref "C34") (pin "1") (pinfunction "1_1") (pintype "passive"))
      (node (ref "R27") (pin "2") (pinfunction "2_2") (pintype "passive"))
    )
    (net (code "17") (name "Net-(D2-PadA)") (class "Default")
      (node (ref "D2") (pin "A") (pinfunction "A_A") (pintype "passive"))
      (node (ref "R5") (pin "2") (pinfunction "2_2") (pintype "passive"))
    )
    (net (code "18") (name "Net-(D3-PadA)") (class "Default")
      (node (ref "D3") (pin "A") (pinfunction "A_A") (pintype "passive"))
      (node (ref "R6") (pin "2") (pinfunction "2_2") (pintype "passive"))
    )
    (net (code "19") (name "Net-(D8-PadA)") (class "Default")
      (node (ref "D8") (pin "A") (pinfunction "A_A") (pintype "passive"))
      (node (ref "R3") (pin "2") (pinfunction "2_2") (pintype "passive"))
    )
    (net (code "20") (name "Net-(D10-PadA)") (class "Default")
      (node (ref "D10") (pin "A") (pinfunction "A_A") (pintype "passive"))
      (node (ref "R4") (pin "2") (pinfunction "2_2") (pintype "passive"))
    )
    (net (code "21") (name "Net-(D11-PadA)") (class "Default")
      (node (ref "D11") (pin "A") (pinfunction "A_A") (pintype "passive"))
      (node (ref "R8") (pin "2") (pinfunction "2_2") (pintype "passive"))
    )
    (net (code "22") (name "Net-(D13-PadA)") (class "Default")
      (node (ref "D13") (pin "A") (pinfunction "A_A") (pintype "passive"))
      (node (ref "R7") (pin "2") (pinfunction "2_2") (pintype "passive"))
    )
    (net (code "23") (name "OUT1") (class "Default")
      (node (ref "C22") (pin "2") (pinfunction "2_2") (pintype "passive"))
      (node (ref "L1") (pin "2") (pinfunction "2_2") (pintype "passive"))
      (node (ref "R25") (pin "2") (pinfunction "2_2") (pintype "passive"))
      (node (ref "U5") (pin "7") (pinfunction "OUT_7") (pintype "output"))
      (node (ref "U6") (pin "2") (pinfunction "2_2") (pintype "passive"))
    )
    (net (code "24") (name "OUT2") (class "Default")
      (node (ref "C31") (pin "2") (pinfunction "2_2") (pintype "passive"))
      (node (ref "L2") (pin "2") (pinfunction "2_2") (pintype "passive"))
      (node (ref "R29") (pin "2") (pinfunction "2_2") (pintype "passive"))
      (node (ref "U7") (pin "7") (pinfunction "OUT_7") (pintype "output"))
      (node (ref "U8") (pin "2") (pinfunction "2_2") (pintype "passive"))
    )
    (net (code "25") (name "REV_GATE") (class "Default")
      (node (ref "D1") (pin "C") (pinfunction "C_C") (pintype "passive"))
      (node (ref "R1") (pin "1") (pinfunction "1_1") (pintype "passive"))
      (node (ref "U$3") (pin "1") (pinfunction "G_1") (pintype "bidirectional"))
    )
    (net (code "26") (name "R_OSC1") (class "Default")
      (node (ref "R24") (pin "2") (pinfunction "2_2") (pintype "passive"))
      (node (ref "U5") (pin "1") (pinfunction "R_OSC_1") (pintype "passive"))
    )
    (net (code "27") (name "R_OSC2") (class "Default")
      (node (ref "R28") (pin "2") (pinfunction "2_2") (pintype "passive"))
      (node (ref "U7") (pin "1") (pinfunction "R_OSC_1") (pintype "passive"))
    )
    (net (code "28") (name "SS1") (class "Default")
      (node (ref "C26") (pin "2") (pinfunction "2_2") (pintype "passive"))
      (node (ref "U5") (pin "12") (pinfunction "SS_12") (pintype "passive"))
    )
    (net (code "29") (name "SS2") (class "Default")
      (node (ref "C35") (pin "2") (pinfunction "2_2") (pintype "passive"))
      (node (ref "U7") (pin "12") (pinfunction "SS_12") (pintype "passive"))
    )
    (net (code "30") (name "VOUT1") (class "Default")
      (node (ref "+7.4VOUT1_TEST") (pin "1") (pinfunction "1_1") (pintype "passive"))
      (node (ref "C29") (pin "1") (pinfunction "1_1") (pintype "passive"))
      (node (ref "C30") (pin "2") (pinfunction "2_2") (pintype "passive"))
      (node (ref "L1") (pin "1") (pinfunction "1_1") (pintype "passive"))
      (node (ref "R2") (pin "3") (pinfunction "3_3") (pintype "passive"))
      (node (ref "R5") (pin "1") (pinfunction "1_1") (pintype "passive"))
    )
    (net (code "31") (name "VOUT2") (class "Default")
      (node (ref "+7.4VOUT2_TEST") (pin "1") (pinfunction "1_1") (pintype "passive"))
      (node (ref "C38") (pin "1") (pinfunction "1_1") (pintype "passive"))
      (node (ref "C39") (pin "2") (pinfunction "2_2") (pintype "passive"))
      (node (ref "L2") (pin "1") (pinfunction "1_1") (pintype "passive"))
      (node (ref "R2") (pin "1") (pinfunction "1_1") (pintype "passive"))
      (node (ref "R6") (pin "1") (pinfunction "1_1") (pintype "passive"))
    )
    (net (code "32") (name "VREF1") (class "Default")
      (node (ref "R25") (pin "1") (pinfunction "1_1") (pintype "passive"))
      (node (ref "R26") (pin "2") (pinfunction "2_2") (pintype "passive"))
      (node (ref "U5") (pin "11") (pinfunction "FB_11") (pintype "input"))
    )
    (net (code "33") (name "VREF2") (class "Default")
      (node (ref "R29") (pin "1") (pinfunction "1_1") (pintype "passive"))
      (node (ref "R30") (pin "2") (pinfunction "2_2") (pintype "passive"))
      (node (ref "U7") (pin "11") (pinfunction "FB_11") (pintype "input"))
    )
    (net (code "34") (name "VSTART1") (class "Default")
      (node (ref "C28") (pin "2") (pinfunction "2_2") (pintype "passive"))
      (node (ref "U5") (pin "15") (pinfunction "VSTART_15") (pintype "output"))
    )
    (net (code "35") (name "VSTART2") (class "Default")
      (node (ref "C37") (pin "2") (pinfunction "2_2") (pintype "passive"))
      (node (ref "U7") (pin "15") (pinfunction "VSTART_15") (pintype "output"))
    )
    (net (code "36") (name "V_REF_CAP1") (class "Default")
      (node (ref "C27") (pin "2") (pinfunction "2_2") (pintype "passive"))
      (node (ref "U5") (pin "14") (pinfunction "VREF_14") (pintype "output"))
    )
    (net (code "37") (name "V_REF_CAP2") (class "Default")
      (node (ref "C36") (pin "2") (pinfunction "2_2") (pintype "passive"))
      (node (ref "U7") (pin "14") (pinfunction "VREF_14") (pintype "output"))
    )
    (net (code "38") (name "unconnected-(BACKPLANE_CONN-Pad08)") (class "Default")
      (node (ref "BACKPLANE_CONN") (pin "08") (pinfunction "08_08") (pintype "passive"))
    )
    (net (code "39") (name "unconnected-(BACKPLANE_CONN-Pad09)") (class "Default")
      (node (ref "BACKPLANE_CONN") (pin "09") (pinfunction "09_09") (pintype "passive"))
    )
    (net (code "40") (name "unconnected-(BACKPLANE_CONN-Pad10)") (class "Default")
      (node (ref "BACKPLANE_CONN") (pin "10") (pinfunction "10_10") (pintype "passive"))
    )
    (net (code "41") (name "unconnected-(BACKPLANE_CONN-Pad11)") (class "Default")
      (node (ref "BACKPLANE_CONN") (pin "11") (pinfunction "11_11") (pintype "passive"))
    )
    (net (code "42") (name "unconnected-(BACKPLANE_CONN-Pad12)") (class "Default")
      (node (ref "BACKPLANE_CONN") (pin "12") (pinfunction "12_12") (pintype "passive"))
    )
    (net (code "43") (name "unconnected-(BACKPLANE_CONN-Pad13)") (class "Default")
      (node (ref "BACKPLANE_CONN") (pin "13") (pinfunction "13_13") (pintype "passive"))
    )
    (net (code "44") (name "unconnected-(U$2-RMCONT-PadPIN2)") (class "Default")
      (node (ref "U$2") (pin "PIN2") (pinfunction "RMCONT_PIN2") (pintype "bidirectional"))
    )
    (net (code "45") (name "unconnected-(U5-RST_DLY-Pad5)") (class "Default")
      (node (ref "U5") (pin "5") (pinfunction "RST_DLY_5") (pintype "input"))
    )
    (net (code "46") (name "unconnected-(U5-RST_OUT-Pad4)") (class "Default")
      (node (ref "U5") (pin "4") (pinfunction "RST_OUT_4") (pintype "passive"))
    )
    (net (code "47") (name "unconnected-(U5-SYNC-Pad13)") (class "Default")
      (node (ref "U5") (pin "13") (pinfunction "SYNC_13") (pintype "input"))
    )
    (net (code "48") (name "unconnected-(U7-RST_DLY-Pad5)") (class "Default")
      (node (ref "U7") (pin "5") (pinfunction "RST_DLY_5") (pintype "input"))
    )
    (net (code "49") (name "unconnected-(U7-RST_OUT-Pad4)") (class "Default")
      (node (ref "U7") (pin "4") (pinfunction "RST_OUT_4") (pintype "passive"))
    )
    (net (code "50") (name "unconnected-(U7-SYNC-Pad13)") (class "Default")
      (node (ref "U7") (pin "13") (pinfunction "SYNC_13") (pintype "input"))
    )
  )
)
